# ai.net
KiCad netlist of a schematic drawn in Altium Designer
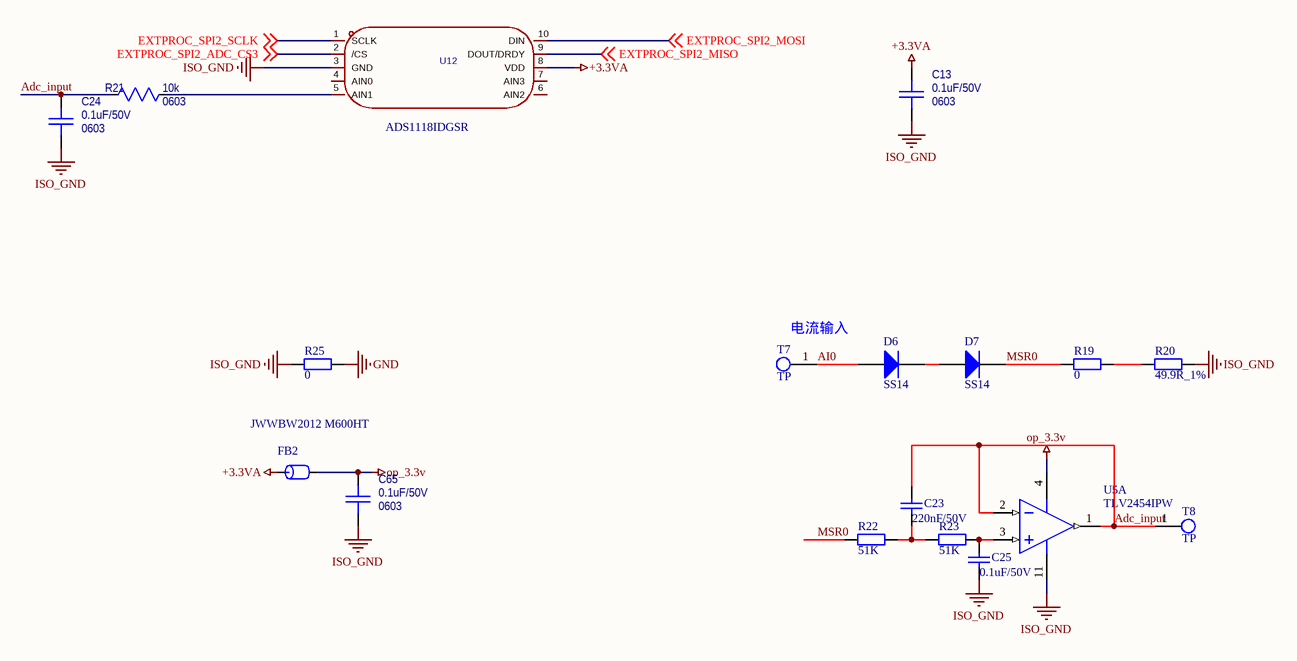
[diagram p0: ai.SchDoc]

(export (version "E")
  (design (tool "Eeschema 10.0.6"))
  (components
    (comp (ref "C13")
      (value "0.1uF/50V")
      (footprint "0603C")
      (description "Capacitor, MLCC")
      (fields (field (name "PACKAGE") "0603"))
      (libsource (lib "Karl") (part "Capacitor_0603"))
    )
    (comp (ref "C23")
      (value "220nF/50V")
      (footprint "0603C")
      (description "Capacitor")
      (libsource (lib "Miscellaneous Devices") (part "Cap"))
    )
    (comp (ref "C24")
      (value "0.1uF/50V")
      (footprint "0603C")
      (description "Capacitor, MLCC")
      (fields (field (name "PACKAGE") "0603"))
      (libsource (lib "Karl") (part "Capacitor_0603"))
    )
    (comp (ref "C25")
      (value "0.1uF/50V")
      (footprint "0603C")
      (description "Capacitor")
      (libsource (lib "Miscellaneous Devices") (part "Cap"))
    )
    (comp (ref "C65")
      (value "0.1uF/50V")
      (footprint "0603C")
      (description "Capacitor, MLCC")
      (fields (field (name "PACKAGE") "0603"))
      (libsource (lib "Karl") (part "Capacitor_0603"))
    )
    (comp (ref "D6")
      (value "SS14")
      (footprint "DO-214AC")
      (description "Default Diode")
      (libsource (lib "Miscellaneous Devices") (part "Diode"))
    )
    (comp (ref "D7")
      (value "SS14")
      (footprint "DO-214AC")
      (description "Default Diode")
      (libsource (lib "Miscellaneous Devices") (part "Diode"))
    )
    (comp (ref "FB2")
      (value "JWWBW2012 M600HT")
      (footprint "0805R")
      (libsource (lib "Schlib_20110825") (part "FB"))
    )
    (comp (ref "R19") (value "0") (footprint "0603R") (libsource (lib "MQlibrary") (part "Res0805M")))
    (comp (ref "R20") (value "49.9R_1%") (footprint "0603R") (libsource (lib "MQlibrary") (part "Res0805M")))
    (comp (ref "R21")
      (value "10k")
      (footprint "0603R")
      (description "Resistor, Standard")
      (fields (field (name "PACKAGE") "0603") (field (name "Comment") "10K/1%"))
      (libsource (lib "Karl") (part "Resistor_0603"))
    )
    (comp (ref "R22") (value "51K") (footprint "0603R") (libsource (lib "MQlibrary") (part "Res0805M")))
    (comp (ref "R23") (value "51K") (footprint "0603R") (libsource (lib "MQlibrary") (part "Res0805M")))
    (comp (ref "R25") (value "0") (footprint "0603R") (libsource (lib "MQlibrary") (part "Res0805M")))
    (comp (ref "T7") (value "TP") (footprint "TPD") (libsource (lib "Schlib_20110825") (part "TP")))
    (comp (ref "T8") (value "TP") (footprint "TPD") (libsource (lib "Schlib_20110825") (part "TP")))
    (comp (ref "U5")
      (value "TLV2454IPW")
      (footprint "TSSOP14")
      (description "Quad High-speed, Ultra Low-power, Single-Supply TTL comparator")
      (libsource (lib "Maxim Analog Comparator") (part "MAX908EPD"))
    )
    (comp (ref "U12")
      (value "ADS1118IDGSR")
      (footprint "VSSOP-10_L3.0-W3.0-P0.50-LS4.9-BL")
      (libsource (lib "altium-import") (part "root_0_ADS1118IDGSR_C55347_"))
    )
  )
  (nets
    (net (code "1") (name "+3.3VA") (class "Default")
      (node (ref "C13") (pin "1") (pinfunction "1_1") (pintype "passive"))
      (node (ref "FB2") (pin "1") (pintype "passive"))
      (node (ref "U12") (pin "8") (pinfunction "VDD_8") (pintype "passive"))
    )
    (net (code "2") (name "/AI0") (class "Default")
      (node (ref "D6") (pin "1") (pinfunction "A_1") (pintype "passive"))
      (node (ref "T7") (pin "1") (pintype "passive"))
    )
    (net (code "3") (name "/Adc_input") (class "Default")
      (node (ref "C23") (pin "2") (pinfunction "2_2") (pintype "passive"))
      (node (ref "C24") (pin "1") (pinfunction "1_1") (pintype "passive"))
      (node (ref "R21") (pin "2") (pinfunction "2_2") (pintype "passive"))
      (node (ref "T8") (pin "1") (pintype "passive"))
      (node (ref "U5") (pin "1") (pinfunction "OUT_1") (pintype "output"))
      (node (ref "U5") (pin "2") (pinfunction "IN-_2") (pintype "input"))
    )
    (net (code "4") (name "/MSR0") (class "Default")
      (node (ref "D7") (pin "2") (pinfunction "K_2") (pintype "passive"))
      (node (ref "R19") (pin "2") (pinfunction "2_2") (pintype "passive"))
      (node (ref "R22") (pin "2") (pinfunction "2_2") (pintype "passive"))
    )
    (net (code "5") (name "EXTPROC_SPI2_ADC_CS3") (class "Default")
      (node (ref "U12") (pin "2") (pinfunction "/CS_2") (pintype "passive"))
    )
    (net (code "6") (name "EXTPROC_SPI2_MISO") (class "Default")
      (node (ref "U12") (pin "9") (pinfunction "DOUT/DRDY_9") (pintype "passive"))
    )
    (net (code "7") (name "EXTPROC_SPI2_MOSI") (class "Default")
      (node (ref "U12") (pin "10") (pinfunction "DIN_10") (pintype "passive"))
    )
    (net (code "8") (name "EXTPROC_SPI2_SCLK") (class "Default")
      (node (ref "U12") (pin "1") (pinfunction "SCLK_1") (pintype "passive"))
    )
    (net (code "9") (name "GND") (class "Default")
      (node (ref "R25") (pin "1") (pinfunction "1_1") (pintype "passive"))
    )
    (net (code "10") (name "ISO_GND") (class "Default")
      (node (ref "C13") (pin "2") (pinfunction "2_2") (pintype "passive"))
      (node (ref "C24") (pin "2") (pinfunction "2_2") (pintype "passive"))
      (node (ref "C25") (pin "1") (pinfunction "1_1") (pintype "passive"))
      (node (ref "C65") (pin "2") (pinfunction "2_2") (pintype "passive"))
      (node (ref "R20") (pin "1") (pinfunction "1_1") (pintype "passive"))
      (node (ref "R25") (pin "2") (pinfunction "2_2") (pintype "passive"))
      (node (ref "U12") (pin "3") (pinfunction "GND_3") (pintype "passive"))
      (node (ref "U5") (pin "11") (pinfunction "GND_11") (pintype "power_in"))
    )
    (net (code "11") (name "Net-(C23-Pad1)") (class "Default")
      (node (ref "C23") (pin "1") (pinfunction "1_1") (pintype "passive"))
      (node (ref "R22") (pin "1") (pinfunction "1_1") (pintype "passive"))
      (node (ref "R23") (pin "2") (pinfunction "2_2") (pintype "passive"))
    )
    (net (code "12") (name "Net-(D6-K)") (class "Default")
      (node (ref "D6") (pin "2") (pinfunction "K_2") (pintype "passive"))
      (node (ref "D7") (pin "1") (pinfunction "A_1") (pintype "passive"))
    )
    (net (code "13") (name "Net-(R19-Pad1)") (class "Default")
      (node (ref "R19") (pin "1") (pinfunction "1_1") (pintype "passive"))
      (node (ref "R20") (pin "2") (pinfunction "2_2") (pintype "passive"))
    )
    (net (code "14") (name "Net-(U5A-IN+)") (class "Default")
      (node (ref "C25") (pin "2") (pinfunction "2_2") (pintype "passive"))
      (node (ref "R23") (pin "1") (pinfunction "1_1") (pintype "passive"))
      (node (ref "U5") (pin "3") (pinfunction "IN+_3") (pintype "input"))
    )
    (net (code "15") (name "Net-(U12-AIN1)") (class "Default")
      (node (ref "R21") (pin "1") (pinfunction "1_1") (pintype "passive"))
      (node (ref "U12") (pin "5") (pinfunction "AIN1_5") (pintype "passive"))
    )
    (net (code "16") (name "op_3.3v") (class "Default")
      (node (ref "C65") (pin "1") (pinfunction "1_1") (pintype "passive"))
      (node (ref "FB2") (pin "2") (pintype "passive"))
      (node (ref "U5") (pin "4") (pinfunction "V+_4") (pintype "power_in"))
    )
    (net (code "17") (name "unconnected-(U12-AIN0-Pad4)") (class "Default")
      (node (ref "U12") (pin "4") (pinfunction "AIN0_4") (pintype "passive"))
    )
    (net (code "18") (name "unconnected-(U12-AIN2-Pad6)") (class "Default")
      (node (ref "U12") (pin "6") (pinfunction "AIN2_6") (pintype "passive"))
    )
    (net (code "19") (name "unconnected-(U12-AIN3-Pad7)") (class "Default")
      (node (ref "U12") (pin "7") (pinfunction "AIN3_7") (pintype "passive"))
    )
  )
)
